# blank_rev_3dip.net
KiCad netlist of a schematic drawn in EAGLE
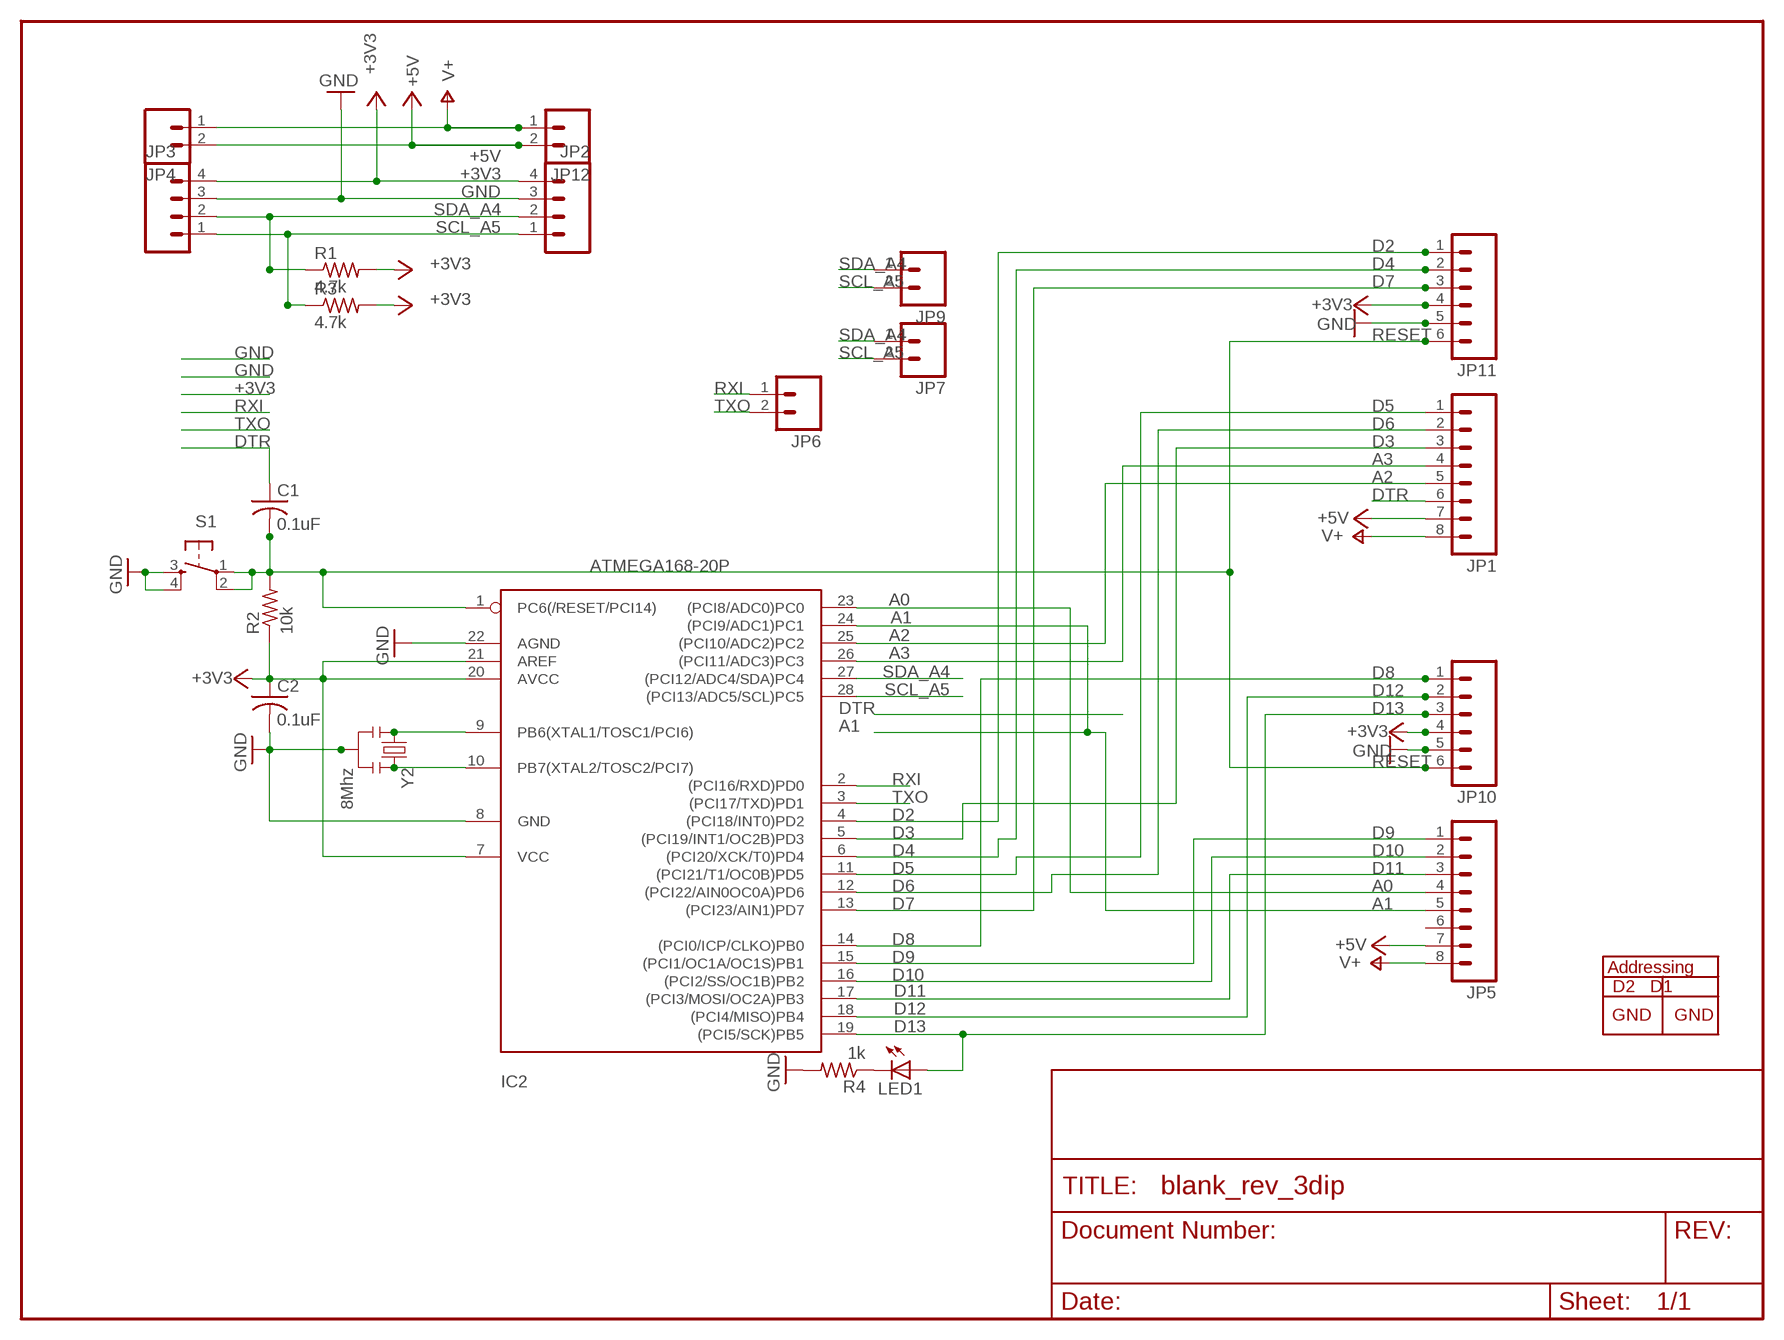
[diagram p0: schematic, sheet 1]

(export (version "E")
  (design (tool "Eeschema 10.0.6"))
  (components
    (comp (ref "C1")
      (value "0.1uF")
      (footprint "eagle-import:C025-024X044")
      (libsource (lib "eagle-import") (part "C-US025-024X044"))
    )
    (comp (ref "C2")
      (value "0.1uF")
      (footprint "eagle-import:C025-024X044")
      (libsource (lib "eagle-import") (part "C-US025-024X044"))
    )
    (comp (ref "IC2")
      (value "ATMEGA168-20P")
      (footprint "eagle-import:DIL28-3")
      (libsource (lib "eagle-import") (part "ATMEGA168P-20"))
    )
    (comp (ref "JP1")
      (value "M081X08")
      (footprint "eagle-import:1X08")
      (libsource (lib "eagle-import") (part "M081X08"))
    )
    (comp (ref "JP2")
      (value "M04PTH")
      (footprint "eagle-import:1X04")
      (libsource (lib "eagle-import") (part "M04PTH"))
    )
    (comp (ref "JP3")
      (value "M04PTH")
      (footprint "eagle-import:1X04")
      (libsource (lib "eagle-import") (part "M04PTH"))
    )
    (comp (ref "JP4")
      (value "M02PTH")
      (footprint "eagle-import:1X02")
      (libsource (lib "eagle-import") (part "M02PTH"))
    )
    (comp (ref "JP5")
      (value "M081X08")
      (footprint "eagle-import:1X08")
      (libsource (lib "eagle-import") (part "M081X08"))
    )
    (comp (ref "JP6")
      (value "M02PTH")
      (footprint "eagle-import:1X02")
      (libsource (lib "eagle-import") (part "M02PTH"))
    )
    (comp (ref "JP7")
      (value "M02PTH")
      (footprint "eagle-import:1X02")
      (libsource (lib "eagle-import") (part "M02PTH"))
    )
    (comp (ref "JP9")
      (value "M02PTH")
      (footprint "eagle-import:1X02")
      (libsource (lib "eagle-import") (part "M02PTH"))
    )
    (comp (ref "JP10")
      (value "M06SIP")
      (footprint "eagle-import:1X06")
      (libsource (lib "eagle-import") (part "M06SIP"))
    )
    (comp (ref "JP11")
      (value "M06SIP")
      (footprint "eagle-import:1X06")
      (libsource (lib "eagle-import") (part "M06SIP"))
    )
    (comp (ref "JP12")
      (value "M02PTH")
      (footprint "eagle-import:1X02")
      (libsource (lib "eagle-import") (part "M02PTH"))
    )
    (comp (ref "LED1")
      (value "LED3MM")
      (footprint "eagle-import:LED3MM")
      (libsource (lib "eagle-import") (part "LED3MM"))
    )
    (comp (ref "R1")
      (value "4.7k")
      (footprint "eagle-import:0204_7")
      (libsource (lib "eagle-import") (part "R-US_0204/7"))
    )
    (comp (ref "R2")
      (value "10k")
      (footprint "eagle-import:0204_7")
      (libsource (lib "eagle-import") (part "R-US_0204/7"))
    )
    (comp (ref "R3")
      (value "4.7k")
      (footprint "eagle-import:0204_7")
      (libsource (lib "eagle-import") (part "R-US_0204/7"))
    )
    (comp (ref "R4")
      (value "1k")
      (footprint "eagle-import:0204_7")
      (libsource (lib "eagle-import") (part "R-US_0204/7"))
    )
    (comp (ref "S1")
      (value "TAC_SWITCHPTH")
      (footprint "eagle-import:TACTILE-PTH")
      (libsource (lib "eagle-import") (part "TAC_SWITCHPTH"))
    )
    (comp (ref "Y2")
      (value "8Mhz")
      (footprint "eagle-import:RESONATOR-PTH")
      (libsource (lib "eagle-import") (part "RESONATORPTH"))
    )
  )
  (nets
    (net (code "1") (name "+3V3") (class "Default")
      (node (ref "C2") (pin "1") (pinfunction "1_1") (pintype "passive"))
      (node (ref "IC2") (pin "20") (pinfunction "AVCC_20") (pintype "bidirectional"))
      (node (ref "IC2") (pin "21") (pinfunction "AREF_21") (pintype "bidirectional"))
      (node (ref "IC2") (pin "7") (pinfunction "VCC_7") (pintype "bidirectional"))
      (node (ref "JP10") (pin "4") (pinfunction "4_4") (pintype "passive"))
      (node (ref "JP11") (pin "4") (pinfunction "4_4") (pintype "passive"))
      (node (ref "JP2") (pin "4") (pinfunction "4_4") (pintype "passive"))
      (node (ref "JP3") (pin "4") (pinfunction "4_4") (pintype "passive"))
      (node (ref "R1") (pin "2") (pinfunction "2_2") (pintype "passive"))
      (node (ref "R2") (pin "1") (pinfunction "1_1") (pintype "passive"))
      (node (ref "R3") (pin "2") (pinfunction "2_2") (pintype "passive"))
    )
    (net (code "2") (name "+5V") (class "Default")
      (node (ref "JP1") (pin "7") (pinfunction "7_7") (pintype "passive"))
      (node (ref "JP12") (pin "2") (pinfunction "2_2") (pintype "passive"))
      (node (ref "JP4") (pin "2") (pinfunction "2_2") (pintype "passive"))
      (node (ref "JP5") (pin "7") (pinfunction "7_7") (pintype "passive"))
    )
    (net (code "3") (name "/A0") (class "Default")
      (node (ref "IC2") (pin "23") (pinfunction "(PCI8/ADC0)PC0_23") (pintype "bidirectional"))
      (node (ref "JP5") (pin "4") (pinfunction "4_4") (pintype "passive"))
    )
    (net (code "4") (name "/A1") (class "Default")
      (node (ref "IC2") (pin "24") (pinfunction "(PCI9/ADC1)PC1_24") (pintype "bidirectional"))
      (node (ref "JP5") (pin "5") (pinfunction "5_5") (pintype "passive"))
    )
    (net (code "5") (name "/A2") (class "Default")
      (node (ref "IC2") (pin "25") (pinfunction "(PCI10/ADC2)PC2_25") (pintype "bidirectional"))
      (node (ref "JP1") (pin "5") (pinfunction "5_5") (pintype "passive"))
    )
    (net (code "6") (name "/A3") (class "Default")
      (node (ref "IC2") (pin "26") (pinfunction "(PCI11/ADC3)PC3_26") (pintype "bidirectional"))
      (node (ref "JP1") (pin "4") (pinfunction "4_4") (pintype "passive"))
    )
    (net (code "7") (name "/D2") (class "Default")
      (node (ref "IC2") (pin "4") (pinfunction "(PCI18/INT0)PD2_4") (pintype "bidirectional"))
      (node (ref "JP11") (pin "1") (pinfunction "1_1") (pintype "passive"))
    )
    (net (code "8") (name "/D3") (class "Default")
      (node (ref "IC2") (pin "5") (pinfunction "(PCI19/INT1/OC2B)PD3_5") (pintype "bidirectional"))
      (node (ref "JP1") (pin "3") (pinfunction "3_3") (pintype "passive"))
    )
    (net (code "9") (name "/D4") (class "Default")
      (node (ref "IC2") (pin "6") (pinfunction "(PCI20/XCK/T0)PD4_6") (pintype "bidirectional"))
      (node (ref "JP11") (pin "2") (pinfunction "2_2") (pintype "passive"))
    )
    (net (code "10") (name "/D5") (class "Default")
      (node (ref "IC2") (pin "11") (pinfunction "(PCI21/T1/OC0B)PD5_11") (pintype "bidirectional"))
      (node (ref "JP1") (pin "1") (pinfunction "1_1") (pintype "passive"))
    )
    (net (code "11") (name "/D6") (class "Default")
      (node (ref "IC2") (pin "12") (pinfunction "(PCI22/AIN0OC0A)PD6_12") (pintype "bidirectional"))
      (node (ref "JP1") (pin "2") (pinfunction "2_2") (pintype "passive"))
    )
    (net (code "12") (name "/D7") (class "Default")
      (node (ref "IC2") (pin "13") (pinfunction "(PCI23/AIN1)PD7_13") (pintype "bidirectional"))
      (node (ref "JP11") (pin "3") (pinfunction "3_3") (pintype "passive"))
    )
    (net (code "13") (name "/D8") (class "Default")
      (node (ref "IC2") (pin "14") (pinfunction "(PCI0/ICP/CLKO)PB0_14") (pintype "bidirectional"))
      (node (ref "JP10") (pin "1") (pinfunction "1_1") (pintype "passive"))
    )
    (net (code "14") (name "/D9") (class "Default")
      (node (ref "IC2") (pin "15") (pinfunction "(PCI1/OC1A/OC1S)PB1_15") (pintype "bidirectional"))
      (node (ref "JP5") (pin "1") (pinfunction "1_1") (pintype "passive"))
    )
    (net (code "15") (name "/D10") (class "Default")
      (node (ref "IC2") (pin "16") (pinfunction "(PCI2/SS/OC1B)PB2_16") (pintype "bidirectional"))
      (node (ref "JP5") (pin "2") (pinfunction "2_2") (pintype "passive"))
    )
    (net (code "16") (name "/D11") (class "Default")
      (node (ref "IC2") (pin "17") (pinfunction "(PCI3/MOSI/OC2A)PB3_17") (pintype "bidirectional"))
      (node (ref "JP5") (pin "3") (pinfunction "3_3") (pintype "passive"))
    )
    (net (code "17") (name "/D12") (class "Default")
      (node (ref "IC2") (pin "18") (pinfunction "(PCI4/MISO)PB4_18") (pintype "bidirectional"))
      (node (ref "JP10") (pin "2") (pinfunction "2_2") (pintype "passive"))
    )
    (net (code "18") (name "/D13") (class "Default")
      (node (ref "IC2") (pin "19") (pinfunction "(PCI5/SCK)PB5_19") (pintype "bidirectional"))
      (node (ref "JP10") (pin "3") (pinfunction "3_3") (pintype "passive"))
      (node (ref "LED1") (pin "A") (pinfunction "A_A") (pintype "passive"))
    )
    (net (code "19") (name "/DTR") (class "Default")
      (node (ref "C1") (pin "1") (pinfunction "1_1") (pintype "passive"))
      (node (ref "JP1") (pin "6") (pinfunction "6_6") (pintype "passive"))
    )
    (net (code "20") (name "/RESET") (class "Default")
      (node (ref "C1") (pin "2") (pinfunction "2_2") (pintype "passive"))
      (node (ref "IC2") (pin "1") (pinfunction "PC6(/RESET/PCI14)_1") (pintype "bidirectional"))
      (node (ref "JP10") (pin "6") (pinfunction "6_6") (pintype "passive"))
      (node (ref "JP11") (pin "6") (pinfunction "6_6") (pintype "passive"))
      (node (ref "R2") (pin "2") (pinfunction "2_2") (pintype "passive"))
      (node (ref "S1") (pin "1") (pinfunction "1_1") (pintype "passive"))
      (node (ref "S1") (pin "2") (pinfunction "2_2") (pintype "passive"))
    )
    (net (code "21") (name "/RXI") (class "Default")
      (node (ref "IC2") (pin "2") (pinfunction "(PCI16/RXD)PD0_2") (pintype "bidirectional"))
      (node (ref "JP6") (pin "1") (pinfunction "1_1") (pintype "passive"))
    )
    (net (code "22") (name "/SCL_A5") (class "Default")
      (node (ref "IC2") (pin "28") (pinfunction "(PCI13/ADC5/SCL)PC5_28") (pintype "bidirectional"))
      (node (ref "JP2") (pin "1") (pinfunction "1_1") (pintype "passive"))
      (node (ref "JP3") (pin "1") (pinfunction "1_1") (pintype "passive"))
      (node (ref "JP7") (pin "2") (pinfunction "2_2") (pintype "passive"))
      (node (ref "JP9") (pin "2") (pinfunction "2_2") (pintype "passive"))
      (node (ref "R3") (pin "1") (pinfunction "1_1") (pintype "passive"))
    )
    (net (code "23") (name "/SDA_A4") (class "Default")
      (node (ref "IC2") (pin "27") (pinfunction "(PCI12/ADC4/SDA)PC4_27") (pintype "bidirectional"))
      (node (ref "JP2") (pin "2") (pinfunction "2_2") (pintype "passive"))
      (node (ref "JP3") (pin "2") (pinfunction "2_2") (pintype "passive"))
      (node (ref "JP7") (pin "1") (pinfunction "1_1") (pintype "passive"))
      (node (ref "JP9") (pin "1") (pinfunction "1_1") (pintype "passive"))
      (node (ref "R1") (pin "1") (pinfunction "1_1") (pintype "passive"))
    )
    (net (code "24") (name "/TXO") (class "Default")
      (node (ref "IC2") (pin "3") (pinfunction "(PCI17/TXD)PD1_3") (pintype "bidirectional"))
      (node (ref "JP6") (pin "2") (pinfunction "2_2") (pintype "passive"))
    )
    (net (code "25") (name "GND") (class "Default")
      (node (ref "C2") (pin "2") (pinfunction "2_2") (pintype "passive"))
      (node (ref "IC2") (pin "22") (pinfunction "AGND_22") (pintype "bidirectional"))
      (node (ref "IC2") (pin "8") (pinfunction "GND_8") (pintype "bidirectional"))
      (node (ref "JP10") (pin "5") (pinfunction "5_5") (pintype "passive"))
      (node (ref "JP11") (pin "5") (pinfunction "5_5") (pintype "passive"))
      (node (ref "JP2") (pin "3") (pinfunction "3_3") (pintype "passive"))
      (node (ref "JP3") (pin "3") (pinfunction "3_3") (pintype "passive"))
      (node (ref "R4") (pin "2") (pinfunction "2_2") (pintype "passive"))
      (node (ref "S1") (pin "3") (pinfunction "3_3") (pintype "passive"))
      (node (ref "S1") (pin "4") (pinfunction "4_4") (pintype "passive"))
      (node (ref "Y2") (pin "2") (pinfunction "2_2") (pintype "passive"))
    )
    (net (code "26") (name "Net-(IC2-PB6(XTAL1{slash}TOSC1{slash}PCI6))") (class "Default")
      (node (ref "IC2") (pin "9") (pinfunction "PB6(XTAL1/TOSC1/PCI6)_9") (pintype "bidirectional"))
      (node (ref "Y2") (pin "1") (pinfunction "1_1") (pintype "passive"))
    )
    (net (code "27") (name "Net-(IC2-PB7(XTAL2{slash}TOSC2{slash}PCI7))") (class "Default")
      (node (ref "IC2") (pin "10") (pinfunction "PB7(XTAL2/TOSC2/PCI7)_10") (pintype "bidirectional"))
      (node (ref "Y2") (pin "3") (pinfunction "3_3") (pintype "passive"))
    )
    (net (code "28") (name "Net-(LED1-C)") (class "Default")
      (node (ref "LED1") (pin "K") (pinfunction "C_K") (pintype "passive"))
      (node (ref "R4") (pin "1") (pinfunction "1_1") (pintype "passive"))
    )
    (net (code "29") (name "V+") (class "Default")
      (node (ref "JP1") (pin "8") (pinfunction "8_8") (pintype "passive"))
      (node (ref "JP12") (pin "1") (pinfunction "1_1") (pintype "passive"))
      (node (ref "JP4") (pin "1") (pinfunction "1_1") (pintype "passive"))
      (node (ref "JP5") (pin "8") (pinfunction "8_8") (pintype "passive"))
    )
    (net (code "30") (name "unconnected-(JP5-Pad6)") (class "Default")
      (node (ref "JP5") (pin "6") (pinfunction "6_6") (pintype "passive"))
    )
  )
)
